# temp.net
KiCad netlist of a schematic drawn in EAGLE
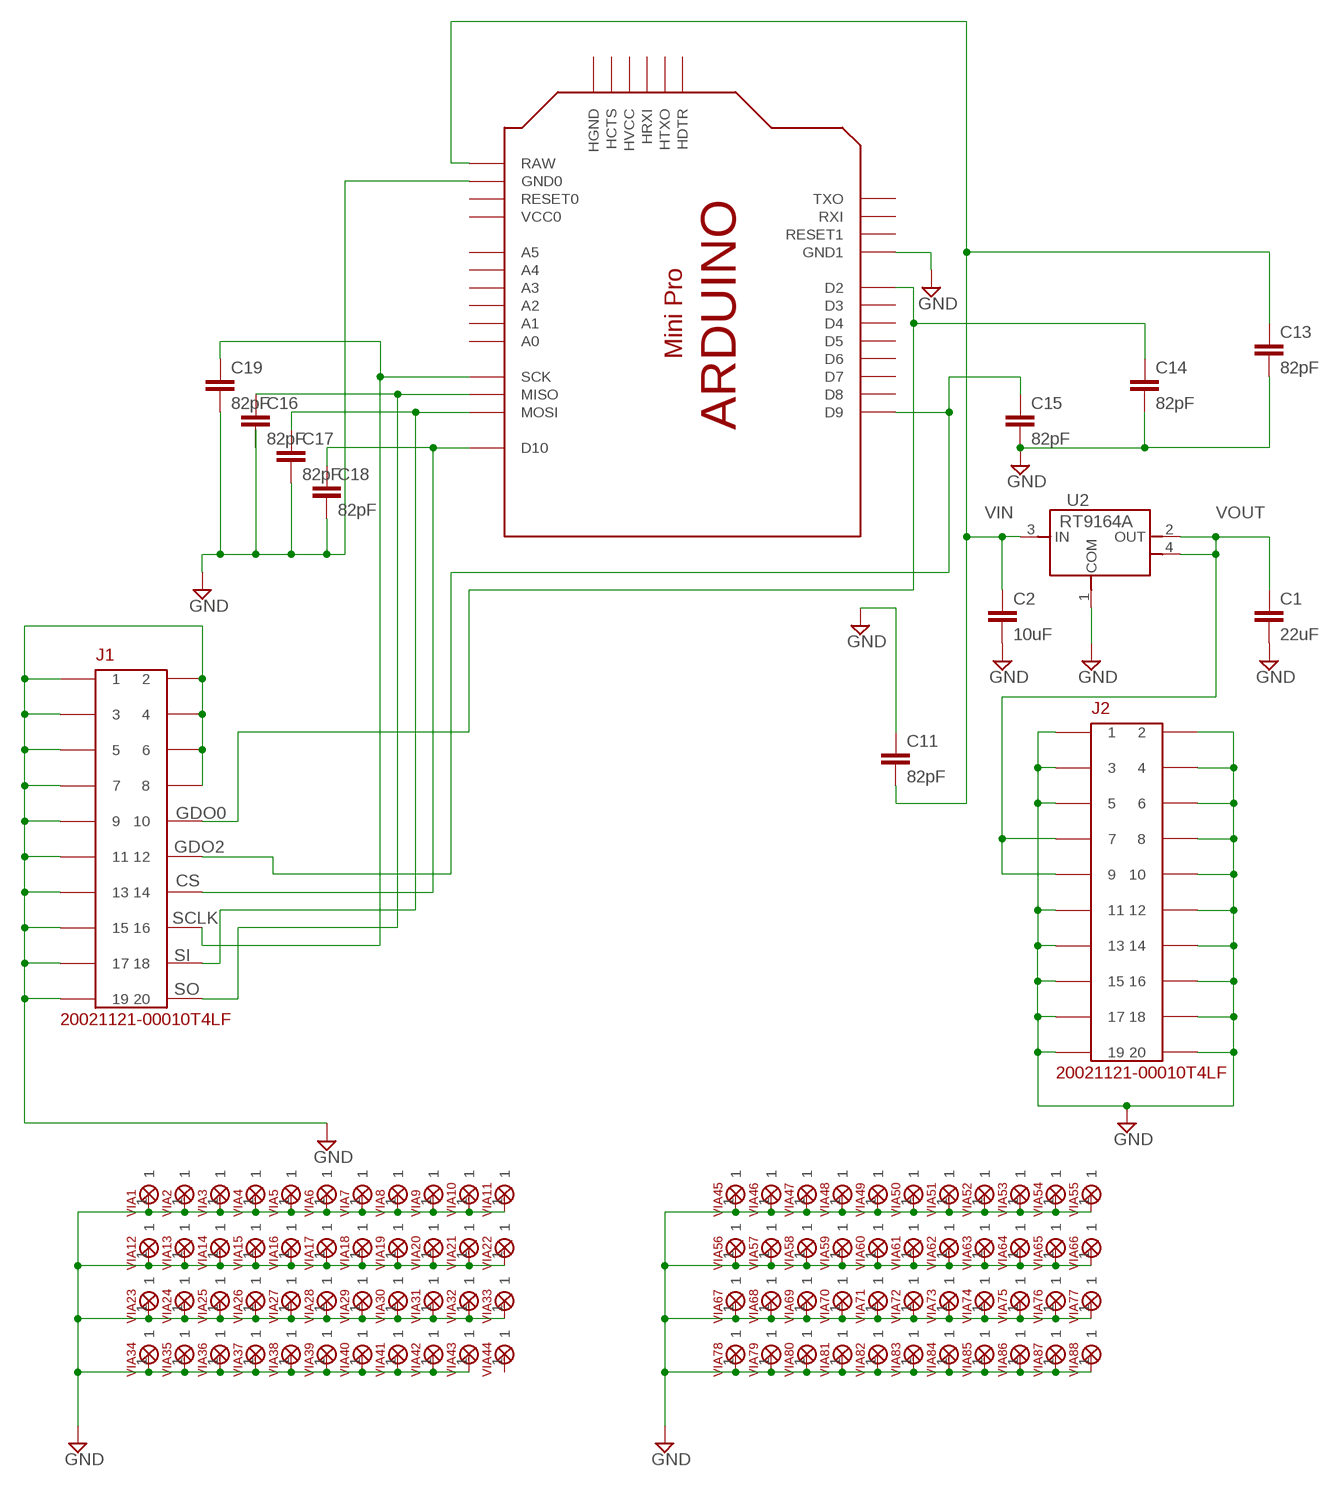
[diagram p0: schematic, sheet 1]

(export (version "E")
  (design (tool "Eeschema 10.0.6"))
  (components
    (comp (ref "C1")
      (value "22uF")
      (footprint "eagle-import:C1206")
      (libsource (lib "eagle-import") (part "CC1206"))
    )
    (comp (ref "C2")
      (value "10uF")
      (footprint "eagle-import:C1206")
      (libsource (lib "eagle-import") (part "CC1206"))
    )
    (comp (ref "C11")
      (value "82pF")
      (footprint "eagle-import:C0805")
      (libsource (lib "eagle-import") (part "C"))
    )
    (comp (ref "C13")
      (value "82pF")
      (footprint "eagle-import:C0805")
      (libsource (lib "eagle-import") (part "C"))
    )
    (comp (ref "C14")
      (value "82pF")
      (footprint "eagle-import:C0805")
      (libsource (lib "eagle-import") (part "C"))
    )
    (comp (ref "C15")
      (value "82pF")
      (footprint "eagle-import:C0805")
      (libsource (lib "eagle-import") (part "C"))
    )
    (comp (ref "C16")
      (value "82pF")
      (footprint "eagle-import:C0805")
      (libsource (lib "eagle-import") (part "C"))
    )
    (comp (ref "C17")
      (value "82pF")
      (footprint "eagle-import:C0805")
      (libsource (lib "eagle-import") (part "C"))
    )
    (comp (ref "C18")
      (value "82pF")
      (footprint "eagle-import:C0805")
      (libsource (lib "eagle-import") (part "C"))
    )
    (comp (ref "C19")
      (value "82pF")
      (footprint "eagle-import:C0805")
      (libsource (lib "eagle-import") (part "C"))
    )
    (comp (ref "J1")
      (value "20021121-00010T4LF")
      (footprint "eagle-import:PINHDR10X2_50X50MIL_SMT")
      (libsource (lib "eagle-import") (part "20021121-00010T4LF"))
    )
    (comp (ref "J2")
      (value "20021121-00010T4LF")
      (footprint "eagle-import:PINHDR10X2_50X50MIL_SMT")
      (libsource (lib "eagle-import") (part "20021121-00010T4LF"))
    )
    (comp (ref "U$1")
      (value "ARDUINOMINI")
      (footprint "eagle-import:ARDUINOMINI")
      (libsource (lib "eagle-import") (part "ARDUINOMINI"))
    )
    (comp (ref "U2")
      (value "RT9164A")
      (footprint "eagle-import:TO223")
      (libsource (lib "eagle-import") (part "RT9164A"))
    )
    (comp (ref "VIA1")
      (value "GND_VIA_NO_THERMAL")
      (footprint "eagle-import:VIA_NO_THERMAL")
      (libsource (lib "eagle-import") (part "GND_VIA_NO_THERMAL"))
    )
    (comp (ref "VIA2")
      (value "GND_VIA_NO_THERMAL")
      (footprint "eagle-import:VIA_NO_THERMAL")
      (libsource (lib "eagle-import") (part "GND_VIA_NO_THERMAL"))
    )
    (comp (ref "VIA3")
      (value "GND_VIA_NO_THERMAL")
      (footprint "eagle-import:VIA_NO_THERMAL")
      (libsource (lib "eagle-import") (part "GND_VIA_NO_THERMAL"))
    )
    (comp (ref "VIA4")
      (value "GND_VIA_NO_THERMAL")
      (footprint "eagle-import:VIA_NO_THERMAL")
      (libsource (lib "eagle-import") (part "GND_VIA_NO_THERMAL"))
    )
    (comp (ref "VIA5")
      (value "GND_VIA_NO_THERMAL")
      (footprint "eagle-import:VIA_NO_THERMAL")
      (libsource (lib "eagle-import") (part "GND_VIA_NO_THERMAL"))
    )
    (comp (ref "VIA6")
      (value "GND_VIA_NO_THERMAL")
      (footprint "eagle-import:VIA_NO_THERMAL")
      (libsource (lib "eagle-import") (part "GND_VIA_NO_THERMAL"))
    )
    (comp (ref "VIA7")
      (value "GND_VIA_NO_THERMAL")
      (footprint "eagle-import:VIA_NO_THERMAL")
      (libsource (lib "eagle-import") (part "GND_VIA_NO_THERMAL"))
    )
    (comp (ref "VIA8")
      (value "GND_VIA_NO_THERMAL")
      (footprint "eagle-import:VIA_NO_THERMAL")
      (libsource (lib "eagle-import") (part "GND_VIA_NO_THERMAL"))
    )
    (comp (ref "VIA9")
      (value "GND_VIA_NO_THERMAL")
      (footprint "eagle-import:VIA_NO_THERMAL")
      (libsource (lib "eagle-import") (part "GND_VIA_NO_THERMAL"))
    )
    (comp (ref "VIA10")
      (value "GND_VIA_NO_THERMAL")
      (footprint "eagle-import:VIA_NO_THERMAL")
      (libsource (lib "eagle-import") (part "GND_VIA_NO_THERMAL"))
    )
    (comp (ref "VIA11")
      (value "GND_VIA_NO_THERMAL")
      (footprint "eagle-import:VIA_NO_THERMAL")
      (libsource (lib "eagle-import") (part "GND_VIA_NO_THERMAL"))
    )
    (comp (ref "VIA12")
      (value "GND_VIA_NO_THERMAL")
      (footprint "eagle-import:VIA_NO_THERMAL")
      (libsource (lib "eagle-import") (part "GND_VIA_NO_THERMAL"))
    )
    (comp (ref "VIA13")
      (value "GND_VIA_NO_THERMAL")
      (footprint "eagle-import:VIA_NO_THERMAL")
      (libsource (lib "eagle-import") (part "GND_VIA_NO_THERMAL"))
    )
    (comp (ref "VIA14")
      (value "GND_VIA_NO_THERMAL")
      (footprint "eagle-import:VIA_NO_THERMAL")
      (libsource (lib "eagle-import") (part "GND_VIA_NO_THERMAL"))
    )
    (comp (ref "VIA15")
      (value "GND_VIA_NO_THERMAL")
      (footprint "eagle-import:VIA_NO_THERMAL")
      (libsource (lib "eagle-import") (part "GND_VIA_NO_THERMAL"))
    )
    (comp (ref "VIA16")
      (value "GND_VIA_NO_THERMAL")
      (footprint "eagle-import:VIA_NO_THERMAL")
      (libsource (lib "eagle-import") (part "GND_VIA_NO_THERMAL"))
    )
    (comp (ref "VIA17")
      (value "GND_VIA_NO_THERMAL")
      (footprint "eagle-import:VIA_NO_THERMAL")
      (libsource (lib "eagle-import") (part "GND_VIA_NO_THERMAL"))
    )
    (comp (ref "VIA18")
      (value "GND_VIA_NO_THERMAL")
      (footprint "eagle-import:VIA_NO_THERMAL")
      (libsource (lib "eagle-import") (part "GND_VIA_NO_THERMAL"))
    )
    (comp (ref "VIA19")
      (value "GND_VIA_NO_THERMAL")
      (footprint "eagle-import:VIA_NO_THERMAL")
      (libsource (lib "eagle-import") (part "GND_VIA_NO_THERMAL"))
    )
    (comp (ref "VIA20")
      (value "GND_VIA_NO_THERMAL")
      (footprint "eagle-import:VIA_NO_THERMAL")
      (libsource (lib "eagle-import") (part "GND_VIA_NO_THERMAL"))
    )
    (comp (ref "VIA21")
      (value "GND_VIA_NO_THERMAL")
      (footprint "eagle-import:VIA_NO_THERMAL")
      (libsource (lib "eagle-import") (part "GND_VIA_NO_THERMAL"))
    )
    (comp (ref "VIA22")
      (value "GND_VIA_NO_THERMAL")
      (footprint "eagle-import:VIA_NO_THERMAL")
      (libsource (lib "eagle-import") (part "GND_VIA_NO_THERMAL"))
    )
    (comp (ref "VIA23")
      (value "GND_VIA_NO_THERMAL")
      (footprint "eagle-import:VIA_NO_THERMAL")
      (libsource (lib "eagle-import") (part "GND_VIA_NO_THERMAL"))
    )
    (comp (ref "VIA24")
      (value "GND_VIA_NO_THERMAL")
      (footprint "eagle-import:VIA_NO_THERMAL")
      (libsource (lib "eagle-import") (part "GND_VIA_NO_THERMAL"))
    )
    (comp (ref "VIA25")
      (value "GND_VIA_NO_THERMAL")
      (footprint "eagle-import:VIA_NO_THERMAL")
      (libsource (lib "eagle-import") (part "GND_VIA_NO_THERMAL"))
    )
    (comp (ref "VIA26")
      (value "GND_VIA_NO_THERMAL")
      (footprint "eagle-import:VIA_NO_THERMAL")
      (libsource (lib "eagle-import") (part "GND_VIA_NO_THERMAL"))
    )
    (comp (ref "VIA27")
      (value "GND_VIA_NO_THERMAL")
      (footprint "eagle-import:VIA_NO_THERMAL")
      (libsource (lib "eagle-import") (part "GND_VIA_NO_THERMAL"))
    )
    (comp (ref "VIA28")
      (value "GND_VIA_NO_THERMAL")
      (footprint "eagle-import:VIA_NO_THERMAL")
      (libsource (lib "eagle-import") (part "GND_VIA_NO_THERMAL"))
    )
    (comp (ref "VIA29")
      (value "GND_VIA_NO_THERMAL")
      (footprint "eagle-import:VIA_NO_THERMAL")
      (libsource (lib "eagle-import") (part "GND_VIA_NO_THERMAL"))
    )
    (comp (ref "VIA30")
      (value "GND_VIA_NO_THERMAL")
      (footprint "eagle-import:VIA_NO_THERMAL")
      (libsource (lib "eagle-import") (part "GND_VIA_NO_THERMAL"))
    )
    (comp (ref "VIA31")
      (value "GND_VIA_NO_THERMAL")
      (footprint "eagle-import:VIA_NO_THERMAL")
      (libsource (lib "eagle-import") (part "GND_VIA_NO_THERMAL"))
    )
    (comp (ref "VIA32")
      (value "GND_VIA_NO_THERMAL")
      (footprint "eagle-import:VIA_NO_THERMAL")
      (libsource (lib "eagle-import") (part "GND_VIA_NO_THERMAL"))
    )
    (comp (ref "VIA33")
      (value "GND_VIA_NO_THERMAL")
      (footprint "eagle-import:VIA_NO_THERMAL")
      (libsource (lib "eagle-import") (part "GND_VIA_NO_THERMAL"))
    )
    (comp (ref "VIA34")
      (value "GND_VIA_NO_THERMAL")
      (footprint "eagle-import:VIA_NO_THERMAL")
      (libsource (lib "eagle-import") (part "GND_VIA_NO_THERMAL"))
    )
    (comp (ref "VIA35")
      (value "GND_VIA_NO_THERMAL")
      (footprint "eagle-import:VIA_NO_THERMAL")
      (libsource (lib "eagle-import") (part "GND_VIA_NO_THERMAL"))
    )
    (comp (ref "VIA36")
      (value "GND_VIA_NO_THERMAL")
      (footprint "eagle-import:VIA_NO_THERMAL")
      (libsource (lib "eagle-import") (part "GND_VIA_NO_THERMAL"))
    )
    (comp (ref "VIA37")
      (value "GND_VIA_NO_THERMAL")
      (footprint "eagle-import:VIA_NO_THERMAL")
      (libsource (lib "eagle-import") (part "GND_VIA_NO_THERMAL"))
    )
    (comp (ref "VIA38")
      (value "GND_VIA_NO_THERMAL")
      (footprint "eagle-import:VIA_NO_THERMAL")
      (libsource (lib "eagle-import") (part "GND_VIA_NO_THERMAL"))
    )
    (comp (ref "VIA39")
      (value "GND_VIA_NO_THERMAL")
      (footprint "eagle-import:VIA_NO_THERMAL")
      (libsource (lib "eagle-import") (part "GND_VIA_NO_THERMAL"))
    )
    (comp (ref "VIA40")
      (value "GND_VIA_NO_THERMAL")
      (footprint "eagle-import:VIA_NO_THERMAL")
      (libsource (lib "eagle-import") (part "GND_VIA_NO_THERMAL"))
    )
    (comp (ref "VIA41")
      (value "GND_VIA_NO_THERMAL")
      (footprint "eagle-import:VIA_NO_THERMAL")
      (libsource (lib "eagle-import") (part "GND_VIA_NO_THERMAL"))
    )
    (comp (ref "VIA42")
      (value "GND_VIA_NO_THERMAL")
      (footprint "eagle-import:VIA_NO_THERMAL")
      (libsource (lib "eagle-import") (part "GND_VIA_NO_THERMAL"))
    )
    (comp (ref "VIA43")
      (value "GND_VIA_NO_THERMAL")
      (footprint "eagle-import:VIA_NO_THERMAL")
      (libsource (lib "eagle-import") (part "GND_VIA_NO_THERMAL"))
    )
    (comp (ref "VIA44")
      (value "GND_VIA_NO_THERMAL")
      (footprint "eagle-import:VIA_NO_THERMAL")
      (libsource (lib "eagle-import") (part "GND_VIA_NO_THERMAL"))
    )
    (comp (ref "VIA45")
      (value "GND_VIA_NO_THERMAL")
      (footprint "eagle-import:VIA_NO_THERMAL")
      (libsource (lib "eagle-import") (part "GND_VIA_NO_THERMAL"))
    )
    (comp (ref "VIA46")
      (value "GND_VIA_NO_THERMAL")
      (footprint "eagle-import:VIA_NO_THERMAL")
      (libsource (lib "eagle-import") (part "GND_VIA_NO_THERMAL"))
    )
    (comp (ref "VIA47")
      (value "GND_VIA_NO_THERMAL")
      (footprint "eagle-import:VIA_NO_THERMAL")
      (libsource (lib "eagle-import") (part "GND_VIA_NO_THERMAL"))
    )
    (comp (ref "VIA48")
      (value "GND_VIA_NO_THERMAL")
      (footprint "eagle-import:VIA_NO_THERMAL")
      (libsource (lib "eagle-import") (part "GND_VIA_NO_THERMAL"))
    )
    (comp (ref "VIA49")
      (value "GND_VIA_NO_THERMAL")
      (footprint "eagle-import:VIA_NO_THERMAL")
      (libsource (lib "eagle-import") (part "GND_VIA_NO_THERMAL"))
    )
    (comp (ref "VIA50")
      (value "GND_VIA_NO_THERMAL")
      (footprint "eagle-import:VIA_NO_THERMAL")
      (libsource (lib "eagle-import") (part "GND_VIA_NO_THERMAL"))
    )
    (comp (ref "VIA51")
      (value "GND_VIA_NO_THERMAL")
      (footprint "eagle-import:VIA_NO_THERMAL")
      (libsource (lib "eagle-import") (part "GND_VIA_NO_THERMAL"))
    )
    (comp (ref "VIA52")
      (value "GND_VIA_NO_THERMAL")
      (footprint "eagle-import:VIA_NO_THERMAL")
      (libsource (lib "eagle-import") (part "GND_VIA_NO_THERMAL"))
    )
    (comp (ref "VIA53")
      (value "GND_VIA_NO_THERMAL")
      (footprint "eagle-import:VIA_NO_THERMAL")
      (libsource (lib "eagle-import") (part "GND_VIA_NO_THERMAL"))
    )
    (comp (ref "VIA54")
      (value "GND_VIA_NO_THERMAL")
      (footprint "eagle-import:VIA_NO_THERMAL")
      (libsource (lib "eagle-import") (part "GND_VIA_NO_THERMAL"))
    )
    (comp (ref "VIA55")
      (value "GND_VIA_NO_THERMAL")
      (footprint "eagle-import:VIA_NO_THERMAL")
      (libsource (lib "eagle-import") (part "GND_VIA_NO_THERMAL"))
    )
    (comp (ref "VIA56")
      (value "GND_VIA_NO_THERMAL")
      (footprint "eagle-import:VIA_NO_THERMAL")
      (libsource (lib "eagle-import") (part "GND_VIA_NO_THERMAL"))
    )
    (comp (ref "VIA57")
      (value "GND_VIA_NO_THERMAL")
      (footprint "eagle-import:VIA_NO_THERMAL")
      (libsource (lib "eagle-import") (part "GND_VIA_NO_THERMAL"))
    )
    (comp (ref "VIA58")
      (value "GND_VIA_NO_THERMAL")
      (footprint "eagle-import:VIA_NO_THERMAL")
      (libsource (lib "eagle-import") (part "GND_VIA_NO_THERMAL"))
    )
    (comp (ref "VIA59")
      (value "GND_VIA_NO_THERMAL")
      (footprint "eagle-import:VIA_NO_THERMAL")
      (libsource (lib "eagle-import") (part "GND_VIA_NO_THERMAL"))
    )
    (comp (ref "VIA60")
      (value "GND_VIA_NO_THERMAL")
      (footprint "eagle-import:VIA_NO_THERMAL")
      (libsource (lib "eagle-import") (part "GND_VIA_NO_THERMAL"))
    )
    (comp (ref "VIA61")
      (value "GND_VIA_NO_THERMAL")
      (footprint "eagle-import:VIA_NO_THERMAL")
      (libsource (lib "eagle-import") (part "GND_VIA_NO_THERMAL"))
    )
    (comp (ref "VIA62")
      (value "GND_VIA_NO_THERMAL")
      (footprint "eagle-import:VIA_NO_THERMAL")
      (libsource (lib "eagle-import") (part "GND_VIA_NO_THERMAL"))
    )
    (comp (ref "VIA63")
      (value "GND_VIA_NO_THERMAL")
      (footprint "eagle-import:VIA_NO_THERMAL")
      (libsource (lib "eagle-import") (part "GND_VIA_NO_THERMAL"))
    )
    (comp (ref "VIA64")
      (value "GND_VIA_NO_THERMAL")
      (footprint "eagle-import:VIA_NO_THERMAL")
      (libsource (lib "eagle-import") (part "GND_VIA_NO_THERMAL"))
    )
    (comp (ref "VIA65")
      (value "GND_VIA_NO_THERMAL")
      (footprint "eagle-import:VIA_NO_THERMAL")
      (libsource (lib "eagle-import") (part "GND_VIA_NO_THERMAL"))
    )
    (comp (ref "VIA66")
      (value "GND_VIA_NO_THERMAL")
      (footprint "eagle-import:VIA_NO_THERMAL")
      (libsource (lib "eagle-import") (part "GND_VIA_NO_THERMAL"))
    )
    (comp (ref "VIA67")
      (value "GND_VIA_NO_THERMAL")
      (footprint "eagle-import:VIA_NO_THERMAL")
      (libsource (lib "eagle-import") (part "GND_VIA_NO_THERMAL"))
    )
    (comp (ref "VIA68")
      (value "GND_VIA_NO_THERMAL")
      (footprint "eagle-import:VIA_NO_THERMAL")
      (libsource (lib "eagle-import") (part "GND_VIA_NO_THERMAL"))
    )
    (comp (ref "VIA69")
      (value "GND_VIA_NO_THERMAL")
      (footprint "eagle-import:VIA_NO_THERMAL")
      (libsource (lib "eagle-import") (part "GND_VIA_NO_THERMAL"))
    )
    (comp (ref "VIA70")
      (value "GND_VIA_NO_THERMAL")
      (footprint "eagle-import:VIA_NO_THERMAL")
      (libsource (lib "eagle-import") (part "GND_VIA_NO_THERMAL"))
    )
    (comp (ref "VIA71")
      (value "GND_VIA_NO_THERMAL")
      (footprint "eagle-import:VIA_NO_THERMAL")
      (libsource (lib "eagle-import") (part "GND_VIA_NO_THERMAL"))
    )
    (comp (ref "VIA72")
      (value "GND_VIA_NO_THERMAL")
      (footprint "eagle-import:VIA_NO_THERMAL")
      (libsource (lib "eagle-import") (part "GND_VIA_NO_THERMAL"))
    )
    (comp (ref "VIA73")
      (value "GND_VIA_NO_THERMAL")
      (footprint "eagle-import:VIA_NO_THERMAL")
      (libsource (lib "eagle-import") (part "GND_VIA_NO_THERMAL"))
    )
    (comp (ref "VIA74")
      (value "GND_VIA_NO_THERMAL")
      (footprint "eagle-import:VIA_NO_THERMAL")
      (libsource (lib "eagle-import") (part "GND_VIA_NO_THERMAL"))
    )
    (comp (ref "VIA75")
      (value "GND_VIA_NO_THERMAL")
      (footprint "eagle-import:VIA_NO_THERMAL")
      (libsource (lib "eagle-import") (part "GND_VIA_NO_THERMAL"))
    )
    (comp (ref "VIA76")
      (value "GND_VIA_NO_THERMAL")
      (footprint "eagle-import:VIA_NO_THERMAL")
      (libsource (lib "eagle-import") (part "GND_VIA_NO_THERMAL"))
    )
    (comp (ref "VIA77")
      (value "GND_VIA_NO_THERMAL")
      (footprint "eagle-import:VIA_NO_THERMAL")
      (libsource (lib "eagle-import") (part "GND_VIA_NO_THERMAL"))
    )
    (comp (ref "VIA78")
      (value "GND_VIA_NO_THERMAL")
      (footprint "eagle-import:VIA_NO_THERMAL")
      (libsource (lib "eagle-import") (part "GND_VIA_NO_THERMAL"))
    )
    (comp (ref "VIA79")
      (value "GND_VIA_NO_THERMAL")
      (footprint "eagle-import:VIA_NO_THERMAL")
      (libsource (lib "eagle-import") (part "GND_VIA_NO_THERMAL"))
    )
    (comp (ref "VIA80")
      (value "GND_VIA_NO_THERMAL")
      (footprint "eagle-import:VIA_NO_THERMAL")
      (libsource (lib "eagle-import") (part "GND_VIA_NO_THERMAL"))
    )
    (comp (ref "VIA81")
      (value "GND_VIA_NO_THERMAL")
      (footprint "eagle-import:VIA_NO_THERMAL")
      (libsource (lib "eagle-import") (part "GND_VIA_NO_THERMAL"))
    )
    (comp (ref "VIA82")
      (value "GND_VIA_NO_THERMAL")
      (footprint "eagle-import:VIA_NO_THERMAL")
      (libsource (lib "eagle-import") (part "GND_VIA_NO_THERMAL"))
    )
    (comp (ref "VIA83")
      (value "GND_VIA_NO_THERMAL")
      (footprint "eagle-import:VIA_NO_THERMAL")
      (libsource (lib "eagle-import") (part "GND_VIA_NO_THERMAL"))
    )
    (comp (ref "VIA84")
      (value "GND_VIA_NO_THERMAL")
      (footprint "eagle-import:VIA_NO_THERMAL")
      (libsource (lib "eagle-import") (part "GND_VIA_NO_THERMAL"))
    )
    (comp (ref "VIA85")
      (value "GND_VIA_NO_THERMAL")
      (footprint "eagle-import:VIA_NO_THERMAL")
      (libsource (lib "eagle-import") (part "GND_VIA_NO_THERMAL"))
    )
    (comp (ref "VIA86")
      (value "GND_VIA_NO_THERMAL")
      (footprint "eagle-import:VIA_NO_THERMAL")
      (libsource (lib "eagle-import") (part "GND_VIA_NO_THERMAL"))
    )
    (comp (ref "VIA87")
      (value "GND_VIA_NO_THERMAL")
      (footprint "eagle-import:VIA_NO_THERMAL")
      (libsource (lib "eagle-import") (part "GND_VIA_NO_THERMAL"))
    )
    (comp (ref "VIA88")
      (value "GND_VIA_NO_THERMAL")
      (footprint "eagle-import:VIA_NO_THERMAL")
      (libsource (lib "eagle-import") (part "GND_VIA_NO_THERMAL"))
    )
  )
  (nets
    (net (code "1") (name "/CS") (class "Default")
      (node (ref "C18") (pin "1") (pinfunction "1_1") (pintype "passive"))
      (node (ref "J1") (pin "P$14") (pinfunction "14_P$14") (pintype "bidirectional"))
      (node (ref "U$1") (pin "P$30") (pinfunction "D10_P$30") (pintype "bidirectional"))
    )
    (net (code "2") (name "/GDO0") (class "Default")
      (node (ref "C14") (pin "1") (pinfunction "1_1") (pintype "passive"))
      (node (ref "J1") (pin "P$10") (pinfunction "10_P$10") (pintype "bidirectional"))
      (node (ref "U$1") (pin "P$8") (pinfunction "D2_P$8") (pintype "bidirectional"))
    )
    (net (code "3") (name "/GDO2") (class "Default")
      (node (ref "C15") (pin "1") (pinfunction "1_1") (pintype "passive"))
      (node (ref "J1") (pin "P$12") (pinfunction "12_P$12") (pintype "bidirectional"))
      (node (ref "U$1") (pin "P$1") (pinfunction "D9_P$1") (pintype "bidirectional"))
    )
    (net (code "4") (name "/SCLK") (class "Default")
      (node (ref "C19") (pin "1") (pinfunction "1_1") (pintype "passive"))
      (node (ref "J1") (pin "P$16") (pinfunction "16_P$16") (pintype "bidirectional"))
      (node (ref "U$1") (pin "P$27") (pinfunction "SCK_P$27") (pintype "bidirectional"))
    )
    (net (code "5") (name "/SI") (class "Default")
      (node (ref "C17") (pin "1") (pinfunction "1_1") (pintype "passive"))
      (node (ref "J1") (pin "P$18") (pinfunction "18_P$18") (pintype "bidirectional"))
      (node (ref "U$1") (pin "P$29") (pinfunction "MOSI_P$29") (pintype "bidirectional"))
    )
    (net (code "6") (name "/SO") (class "Default")
      (node (ref "C16") (pin "1") (pinfunction "1_1") (pintype "passive"))
      (node (ref "J1") (pin "P$20") (pinfunction "20_P$20") (pintype "bidirectional"))
      (node (ref "U$1") (pin "P$28") (pinfunction "MISO_P$28") (pintype "bidirectional"))
    )
    (net (code "7") (name "/VIN") (class "Default")
      (node (ref "C11") (pin "2") (pinfunction "2_2") (pintype "passive"))
      (node (ref "C13") (pin "1") (pinfunction "1_1") (pintype "passive"))
      (node (ref "C2") (pin "1") (pinfunction "1_1") (pintype "passive"))
      (node (ref "U$1") (pin "P$19") (pinfunction "RAW_P$19") (pintype "bidirectional"))
      (node (ref "U2") (pin "3") (pinfunction "IN_3") (pintype "input"))
    )
    (net (code "8") (name "/VOUT") (class "Default")
      (node (ref "C1") (pin "1") (pinfunction "1_1") (pintype "passive"))
      (node (ref "J2") (pin "P$7") (pinfunction "7_P$7") (pintype "bidirectional"))
      (node (ref "J2") (pin "P$9") (pinfunction "9_P$9") (pintype "bidirectional"))
      (node (ref "U2") (pin "2") (pinfunction "OUT_2") (pintype "passive"))
      (node (ref "U2") (pin "4") (pinfunction "OUT_4") (pintype "passive"))
    )
    (net (code "9") (name "GND") (class "Default")
      (node (ref "C1") (pin "2") (pinfunction "2_2") (pintype "passive"))
      (node (ref "C11") (pin "1") (pinfunction "1_1") (pintype "passive"))
      (node (ref "C13") (pin "2") (pinfunction "2_2") (pintype "passive"))
      (node (ref "C14") (pin "2") (pinfunction "2_2") (pintype "passive"))
      (node (ref "C15") (pin "2") (pinfunction "2_2") (pintype "passive"))
      (node (ref "C17") (pin "2") (pinfunction "2_2") (pintype "passive"))
      (node (ref "C18") (pin "2") (pinfunction "2_2") (pintype "passive"))
      (node (ref "C19") (pin "2") (pinfunction "2_2") (pintype "passive"))
      (node (ref "C2") (pin "2") (pinfunction "2_2") (pintype "passive"))
      (node (ref "J1") (pin "P$1") (pinfunction "1_P$1") (pintype "bidirectional"))
      (node (ref "J1") (pin "P$11") (pinfunction "11_P$11") (pintype "bidirectional"))
      (node (ref "J1") (pin "P$13") (pinfunction "13_P$13") (pintype "bidirectional"))
      (node (ref "J1") (pin "P$15") (pinfunction "15_P$15") (pintype "bidirectional"))
      (node (ref "J1") (pin "P$17") (pinfunction "17_P$17") (pintype "bidirectional"))
      (node (ref "J1") (pin "P$19") (pinfunction "19_P$19") (pintype "bidirectional"))
      (node (ref "J1") (pin "P$2") (pinfunction "2_P$2") (pintype "bidirectional"))
      (node (ref "J1") (pin "P$3") (pinfunction "3_P$3") (pintype "bidirectional"))
      (node (ref "J1") (pin "P$4") (pinfunction "4_P$4") (pintype "bidirectional"))
      (node (ref "J1") (pin "P$5") (pinfunction "5_P$5") (pintype "bidirectional"))
      (node (ref "J1") (pin "P$6") (pinfunction "6_P$6") (pintype "bidirectional"))
      (node (ref "J1") (pin "P$7") (pinfunction "7_P$7") (pintype "bidirectional"))
      (node (ref "J1") (pin "P$8") (pinfunction "8_P$8") (pintype "bidirectional"))
      (node (ref "J1") (pin "P$9") (pinfunction "9_P$9") (pintype "bidirectional"))
      (node (ref "J2") (pin "P$1") (pinfunction "1_P$1") (pintype "bidirectional"))
      (node (ref "J2") (pin "P$10") (pinfunction "10_P$10") (pintype "bidirectional"))
      (node (ref "J2") (pin "P$11") (pinfunction "11_P$11") (pintype "bidirectional"))
      (node (ref "J2") (pin "P$12") (pinfunction "12_P$12") (pintype "bidirectional"))
      (node (ref "J2") (pin "P$13") (pinfunction "13_P$13") (pintype "bidirectional"))
      (node (ref "J2") (pin "P$14") (pinfunction "14_P$14") (pintype "bidirectional"))
      (node (ref "J2") (pin "P$15") (pinfunction "15_P$15") (pintype "bidirectional"))
      (node (ref "J2") (pin "P$16") (pinfunction "16_P$16") (pintype "bidirectional"))
      (node (ref "J2") (pin "P$17") (pinfunction "17_P$17") (pintype "bidirectional"))
      (node (ref "J2") (pin "P$18") (pinfunction "18_P$18") (pintype "bidirectional"))
      (node (ref "J2") (pin "P$19") (pinfunction "19_P$19") (pintype "bidirectional"))
      (node (ref "J2") (pin "P$2") (pinfunction "2_P$2") (pintype "bidirectional"))
      (node (ref "J2") (pin "P$20") (pinfunction "20_P$20") (pintype "bidirectional"))
      (node (ref "J2") (pin "P$3") (pinfunction "3_P$3") (pintype "bidirectional"))
      (node (ref "J2") (pin "P$4") (pinfunction "4_P$4") (pintype "bidirectional"))
      (node (ref "J2") (pin "P$5") (pinfunction "5_P$5") (pintype "bidirectional"))
      (node (ref "J2") (pin "P$6") (pinfunction "6_P$6") (pintype "bidirectional"))
      (node (ref "J2") (pin "P$8") (pinfunction "8_P$8") (pintype "bidirectional"))
      (node (ref "U$1") (pin "P$20") (pinfunction "GND0_P$20") (pintype "bidirectional"))
      (node (ref "U$1") (pin "P$9") (pinfunction "GND1_P$9") (pintype "bidirectional"))
      (node (ref "U2") (pin "1") (pinfunction "COM_1") (pintype "input"))
      (node (ref "VIA1") (pin "1") (pinfunction "1_1") (pintype "bidirectional"))
      (node (ref "VIA10") (pin "1") (pinfunction "1_1") (pintype "bidirectional"))
      (node (ref "VIA11") (pin "1") (pinfunction "1_1") (pintype "bidirectional"))
      (node (ref "VIA12") (pin "1") (pinfunction "1_1") (pintype "bidirectional"))
      (node (ref "VIA13") (pin "1") (pinfunction "1_1") (pintype "bidirectional"))
      (node (ref "VIA14") (pin "1") (pinfunction "1_1") (pintype "bidirectional"))
      (node (ref "VIA15") (pin "1") (pinfunction "1_1") (pintype "bidirectional"))
      (node (ref "VIA16") (pin "1") (pinfunction "1_1") (pintype "bidirectional"))
      (node (ref "VIA17") (pin "1") (pinfunction "1_1") (pintype "bidirectional"))
      (node (ref "VIA18") (pin "1") (pinfunction "1_1") (pintype "bidirectional"))
      (node (ref "VIA19") (pin "1") (pinfunction "1_1") (pintype "bidirectional"))
      (node (ref "VIA2") (pin "1") (pinfunction "1_1") (pintype "bidirectional"))
      (node (ref "VIA20") (pin "1") (pinfunction "1_1") (pintype "bidirectional"))
      (node (ref "VIA21") (pin "1") (pinfunction "1_1") (pintype "bidirectional"))
      (node (ref "VIA22") (pin "1") (pinfunction "1_1") (pintype "bidirectional"))
      (node (ref "VIA23") (pin "1") (pinfunction "1_1") (pintype "bidirectional"))
      (node (ref "VIA24") (pin "1") (pinfunction "1_1") (pintype "bidirectional"))
      (node (ref "VIA25") (pin "1") (pinfunction "1_1") (pintype "bidirectional"))
      (node (ref "VIA26") (pin "1") (pinfunction "1_1") (pintype "bidirectional"))
      (node (ref "VIA27") (pin "1") (pinfunction "1_1") (pintype "bidirectional"))
      (node (ref "VIA28") (pin "1") (pinfunction "1_1") (pintype "bidirectional"))
      (node (ref "VIA29") (pin "1") (pinfunction "1_1") (pintype "bidirectional"))
      (node (ref "VIA3") (pin "1") (pinfunction "1_1") (pintype "bidirectional"))
      (node (ref "VIA30") (pin "1") (pinfunction "1_1") (pintype "bidirectional"))
      (node (ref "VIA31") (pin "1") (pinfunction "1_1") (pintype "bidirectional"))
      (node (ref "VIA32") (pin "1") (pinfunction "1_1") (pintype "bidirectional"))
      (node (ref "VIA33") (pin "1") (pinfunction "1_1") (pintype "bidirectional"))
      (node (ref "VIA34") (pin "1") (pinfunction "1_1") (pintype "bidirectional"))
      (node (ref "VIA35") (pin "1") (pinfunction "1_1") (pintype "bidirectional"))
      (node (ref "VIA36") (pin "1") (pinfunction "1_1") (pintype "bidirectional"))
      (node (ref "VIA37") (pin "1") (pinfunction "1_1") (pintype "bidirectional"))
      (node (ref "VIA38") (pin "1") (pinfunction "1_1") (pintype "bidirectional"))
      (node (ref "VIA39") (pin "1") (pinfunction "1_1") (pintype "bidirectional"))
      (node (ref "VIA4") (pin "1") (pinfunction "1_1") (pintype "bidirectional"))
      (node (ref "VIA40") (pin "1") (pinfunction "1_1") (pintype "bidirectional"))
      (node (ref "VIA41") (pin "1") (pinfunction "1_1") (pintype "bidirectional"))
      (node (ref "VIA42") (pin "1") (pinfunction "1_1") (pintype "bidirectional"))
      (node (ref "VIA43") (pin "1") (pinfunction "1_1") (pintype "bidirectional"))
      (node (ref "VIA45") (pin "1") (pinfunction "1_1") (pintype "bidirectional"))
      (node (ref "VIA46") (pin "1") (pinfunction "1_1") (pintype "bidirectional"))
      (node (ref "VIA47") (pin "1") (pinfunction "1_1") (pintype "bidirectional"))
      (node (ref "VIA48") (pin "1") (pinfunction "1_1") (pintype "bidirectional"))
      (node (ref "VIA49") (pin "1") (pinfunction "1_1") (pintype "bidirectional"))
      (node (ref "VIA5") (pin "1") (pinfunction "1_1") (pintype "bidirectional"))
      (node (ref "VIA50") (pin "1") (pinfunction "1_1") (pintype "bidirectional"))
      (node (ref "VIA51") (pin "1") (pinfunction "1_1") (pintype "bidirectional"))
      (node (ref "VIA52") (pin "1") (pinfunction "1_1") (pintype "bidirectional"))
      (node (ref "VIA53") (pin "1") (pinfunction "1_1") (pintype "bidirectional"))
      (node (ref "VIA54") (pin "1") (pinfunction "1_1") (pintype "bidirectional"))
      (node (ref "VIA55") (pin "1") (pinfunction "1_1") (pintype "bidirectional"))
      (node (ref "VIA56") (pin "1") (pinfunction "1_1") (pintype "bidirectional"))
      (node (ref "VIA57") (pin "1") (pinfunction "1_1") (pintype "bidirectional"))
      (node (ref "VIA58") (pin "1") (pinfunction "1_1") (pintype "bidirectional"))
      (node (ref "VIA59") (pin "1") (pinfunction "1_1") (pintype "bidirectional"))
      (node (ref "VIA6") (pin "1") (pinfunction "1_1") (pintype "bidirectional"))
      (node (ref "VIA60") (pin "1") (pinfunction "1_1") (pintype "bidirectional"))
      (node (ref "VIA61") (pin "1") (pinfunction "1_1") (pintype "bidirectional"))
      (node (ref "VIA62") (pin "1") (pinfunction "1_1") (pintype "bidirectional"))
      (node (ref "VIA63") (pin "1") (pinfunction "1_1") (pintype "bidirectional"))
      (node (ref "VIA64") (pin "1") (pinfunction "1_1") (pintype "bidirectional"))
      (node (ref "VIA65") (pin "1") (pinfunction "1_1") (pintype "bidirectional"))
      (node (ref "VIA66") (pin "1") (pinfunction "1_1") (pintype "bidirectional"))
      (node (ref "VIA67") (pin "1") (pinfunction "1_1") (pintype "bidirectional"))
      (node (ref "VIA68") (pin "1") (pinfunction "1_1") (pintype "bidirectional"))
      (node (ref "VIA69") (pin "1") (pinfunction "1_1") (pintype "bidirectional"))
      (node (ref "VIA7") (pin "1") (pinfunction "1_1") (pintype "bidirectional"))
      (node (ref "VIA70") (pin "1") (pinfunction "1_1") (pintype "bidirectional"))
      (node (ref "VIA71") (pin "1") (pinfunction "1_1") (pintype "bidirectional"))
      (node (ref "VIA72") (pin "1") (pinfunction "1_1") (pintype "bidirectional"))
      (node (ref "VIA73") (pin "1") (pinfunction "1_1") (pintype "bidirectional"))
      (node (ref "VIA74") (pin "1") (pinfunction "1_1") (pintype "bidirectional"))
      (node (ref "VIA75") (pin "1") (pinfunction "1_1") (pintype "bidirectional"))
      (node (ref "VIA76") (pin "1") (pinfunction "1_1") (pintype "bidirectional"))
      (node (ref "VIA77") (pin "1") (pinfunction "1_1") (pintype "bidirectional"))
      (node (ref "VIA78") (pin "1") (pinfunction "1_1") (pintype "bidirectional"))
      (node (ref "VIA79") (pin "1") (pinfunction "1_1") (pintype "bidirectional"))
      (node (ref "VIA8") (pin "1") (pinfunction "1_1") (pintype "bidirectional"))
      (node (ref "VIA80") (pin "1") (pinfunction "1_1") (pintype "bidirectional"))
      (node (ref "VIA81") (pin "1") (pinfunction "1_1") (pintype "bidirectional"))
      (node (ref "VIA82") (pin "1") (pinfunction "1_1") (pintype "bidirectional"))
      (node (ref "VIA83") (pin "1") (pinfunction "1_1") (pintype "bidirectional"))
      (node (ref "VIA84") (pin "1") (pinfunction "1_1") (pintype "bidirectional"))
      (node (ref "VIA85") (pin "1") (pinfunction "1_1") (pintype "bidirectional"))
      (node (ref "VIA86") (pin "1") (pinfunction "1_1") (pintype "bidirectional"))
      (node (ref "VIA87") (pin "1") (pinfunction "1_1") (pintype "bidirectional"))
      (node (ref "VIA88") (pin "1") (pinfunction "1_1") (pintype "bidirectional"))
      (node (ref "VIA9") (pin "1") (pinfunction "1_1") (pintype "bidirectional"))
    )
    (net (code "10") (name "unconnected-(C16-Pad2)") (class "Default")
      (node (ref "C16") (pin "2") (pinfunction "2_2") (pintype "passive"))
    )
    (net (code "11") (name "unconnected-(U$1-A0-PadP$26)") (class "Default")
      (node (ref "U$1") (pin "P$26") (pinfunction "A0_P$26") (pintype "bidirectional"))
    )
    (net (code "12") (name "unconnected-(U$1-A1-PadP$25)") (class "Default")
      (node (ref "U$1") (pin "P$25") (pinfunction "A1_P$25") (pintype "bidirectional"))
    )
    (net (code "13") (name "unconnected-(U$1-A2-PadP$24)") (class "Default")
      (node (ref "U$1") (pin "P$24") (pinfunction "A2_P$24") (pintype "bidirectional"))
    )
    (net (code "14") (name "unconnected-(U$1-A3-PadP$23)") (class "Default")
      (node (ref "U$1") (pin "P$23") (pinfunction "A3_P$23") (pintype "bidirectional"))
    )
    (net (code "15") (name "unconnected-(U$1-A4-PadP$34)") (class "Default")
      (node (ref "U$1") (pin "P$34") (pinfunction "A4_P$34") (pintype "bidirectional"))
    )
    (net (code "16") (name "unconnected-(U$1-A5-PadP$35)") (class "Default")
      (node (ref "U$1") (pin "P$35") (pinfunction "A5_P$35") (pintype "bidirectional"))
    )
    (net (code "17") (name "unconnected-(U$1-D3-PadP$7)") (class "Default")
      (node (ref "U$1") (pin "P$7") (pinfunction "D3_P$7") (pintype "bidirectional"))
    )
    (net (code "18") (name "unconnected-(U$1-D4-PadP$6)") (class "Default")
      (node (ref "U$1") (pin "P$6") (pinfunction "D4_P$6") (pintype "bidirectional"))
    )
    (net (code "19") (name "unconnected-(U$1-D5-PadP$5)") (class "Default")
      (node (ref "U$1") (pin "P$5") (pinfunction "D5_P$5") (pintype "bidirectional"))
    )
    (net (code "20") (name "unconnected-(U$1-D6-PadP$4)") (class "Default")
      (node (ref "U$1") (pin "P$4") (pinfunction "D6_P$4") (pintype "bidirectional"))
    )
    (net (code "21") (name "unconnected-(U$1-D7-PadP$3)") (class "Default")
      (node (ref "U$1") (pin "P$3") (pinfunction "D7_P$3") (pintype "bidirectional"))
    )
    (net (code "22") (name "unconnected-(U$1-D8-PadP$2)") (class "Default")
      (node (ref "U$1") (pin "P$2") (pinfunction "D8_P$2") (pintype "bidirectional"))
    )
    (net (code "23") (name "unconnected-(U$1-HCTS-PadP$17)") (class "Default")
      (node (ref "U$1") (pin "P$17") (pinfunction "HCTS_P$17") (pintype "bidirectional"))
    )
    (net (code "24") (name "unconnected-(U$1-HDTR-PadP$13)") (class "Default")
      (node (ref "U$1") (pin "P$13") (pinfunction "HDTR_P$13") (pintype "bidirectional"))
    )
    (net (code "25") (name "unconnected-(U$1-HGND-PadP$18)") (class "Default")
      (node (ref "U$1") (pin "P$18") (pinfunction "HGND_P$18") (pintype "bidirectional"))
    )
    (net (code "26") (name "unconnected-(U$1-HRXI-PadP$15)") (class "Default")
      (node (ref "U$1") (pin "P$15") (pinfunction "HRXI_P$15") (pintype "bidirectional"))
    )
    (net (code "27") (name "unconnected-(U$1-HTXO-PadP$14)") (class "Default")
      (node (ref "U$1") (pin "P$14") (pinfunction "HTXO_P$14") (pintype "bidirectional"))
    )
    (net (code "28") (name "unconnected-(U$1-HVCC-PadP$16)") (class "Default")
      (node (ref "U$1") (pin "P$16") (pinfunction "HVCC_P$16") (pintype "bidirectional"))
    )
    (net (code "29") (name "unconnected-(U$1-RESET0-PadP$21)") (class "Default")
      (node (ref "U$1") (pin "P$21") (pinfunction "RESET0_P$21") (pintype "bidirectional"))
    )
    (net (code "30") (name "unconnected-(U$1-RESET1-PadP$10)") (class "Default")
      (node (ref "U$1") (pin "P$10") (pinfunction "RESET1_P$10") (pintype "bidirectional"))
    )
    (net (code "31") (name "unconnected-(U$1-RXI-PadP$11)") (class "Default")
      (node (ref "U$1") (pin "P$11") (pinfunction "RXI_P$11") (pintype "bidirectional"))
    )
    (net (code "32") (name "unconnected-(U$1-TXO-PadP$12)") (class "Default")
      (node (ref "U$1") (pin "P$12") (pinfunction "TXO_P$12") (pintype "bidirectional"))
    )
    (net (code "33") (name "unconnected-(U$1-VCC0-PadP$22)") (class "Default")
      (node (ref "U$1") (pin "P$22") (pinfunction "VCC0_P$22") (pintype "bidirectional"))
    )
    (net (code "34") (name "unconnected-(VIA44-Pad1)") (class "Default")
      (node (ref "VIA44") (pin "1") (pinfunction "1_1") (pintype "bidirectional"))
    )
  )
)
